# Sheet2.net
KiCad netlist of a schematic drawn in Altium Designer
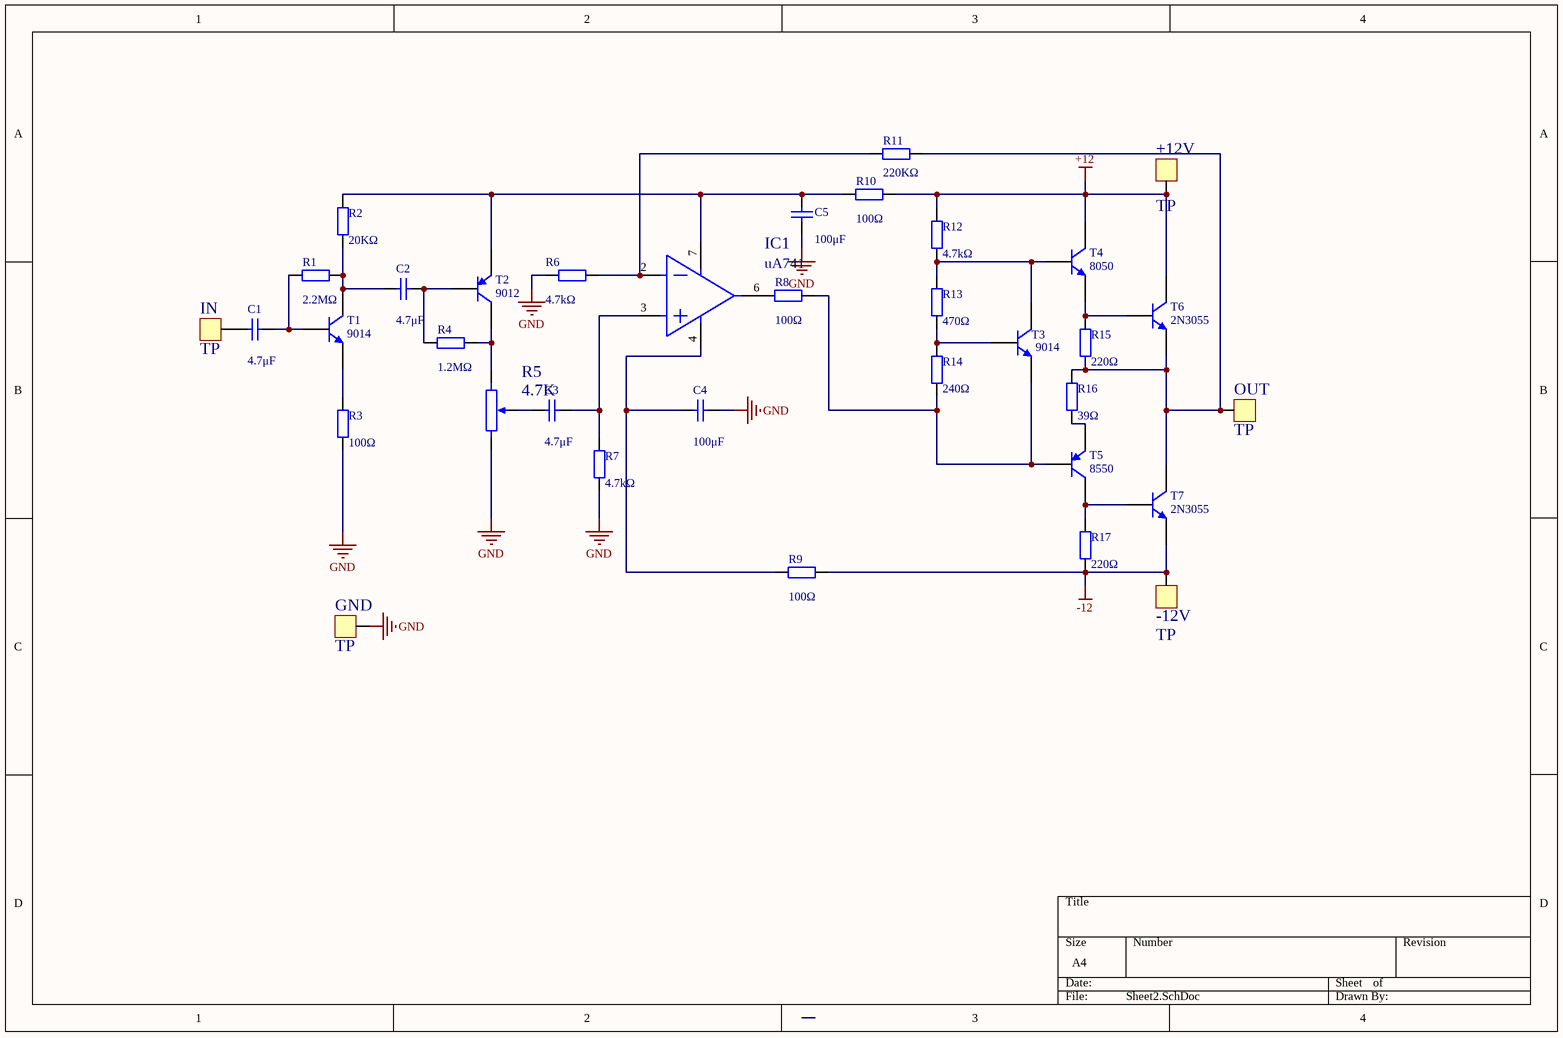
[diagram p0: Sheet2.SchDoc]

(export (version "E")
  (design (tool "Eeschema 10.0.6"))
  (components
    (comp (ref "+12V") (value "TP") (footprint "TP2") (libsource (lib "") (part "TP_2")))
    (comp (ref "-12V") (value "TP") (footprint "TP2") (libsource (lib "") (part "TP_3")))
    (comp (ref "C1")
      (value "4.7μF")
      (footprint "teach2018:CAPPR5-5x5")
      (description "Capacitor")
      (fields (field (name "PUBLISHER") "Altium Limited"))
      (libsource (lib "Miscellaneous Devices") (part "Cap"))
    )
    (comp (ref "C2")
      (value "4.7μF")
      (footprint "teach2018:CAPPR5-5x5")
      (description "Capacitor")
      (fields (field (name "PUBLISHER") "Altium Limited"))
      (libsource (lib "Miscellaneous Devices") (part "Cap"))
    )
    (comp (ref "C3")
      (value "4.7μF")
      (footprint "teach2018:CAPPR5-5x5")
      (description "Capacitor")
      (fields (field (name "PUBLISHER") "Altium Limited"))
      (libsource (lib "Miscellaneous Devices") (part "Cap"))
    )
    (comp (ref "C4")
      (value "100μF")
      (footprint "teach2018:CAPPR5-5x5")
      (description "Capacitor")
      (fields (field (name "PUBLISHER") "Altium Limited"))
      (libsource (lib "Miscellaneous Devices") (part "Cap"))
    )
    (comp (ref "C5")
      (value "100μF")
      (footprint "teach2018:CAPPR5-5x5")
      (description "Capacitor")
      (fields (field (name "PUBLISHER") "Altium Limited"))
      (libsource (lib "Miscellaneous Devices") (part "Cap"))
    )
    (comp (ref "GND") (value "TP") (footprint "TP2") (libsource (lib "teach2018") (part "TP")))
    (comp (ref "IC1")
      (value "uA741")
      (footprint "DIP-8")
      (description "OAP")
      (libsource (lib "teach2018") (part "uA741"))
    )
    (comp (ref "IN") (value "TP") (footprint "TP2") (libsource (lib "teach2018") (part "TP")))
    (comp (ref "OUT") (value "TP") (footprint "TP2") (libsource (lib "") (part "TP_1")))
    (comp (ref "R1")
      (value "2.2MΩ")
      (footprint "AXIAL-0.4")
      (description "Resistor")
      (fields (field (name "PUBLISHER") "Altium Limited"))
      (libsource (lib "") (part "Res2_1"))
    )
    (comp (ref "R2")
      (value "20KΩ")
      (footprint "AXIAL-0.4")
      (description "Resistor")
      (fields (field (name "PUBLISHER") "Altium Limited"))
      (libsource (lib "Miscellaneous Devices") (part "Res2"))
    )
    (comp (ref "R3")
      (value "100Ω")
      (footprint "AXIAL-0.4")
      (description "Resistor")
      (fields (field (name "PUBLISHER") "Altium Limited"))
      (libsource (lib "Miscellaneous Devices") (part "Res2"))
    )
    (comp (ref "R4")
      (value "1.2MΩ")
      (footprint "AXIAL-0.4")
      (description "Resistor")
      (fields (field (name "PUBLISHER") "Altium Limited"))
      (libsource (lib "") (part "Res2_1"))
    )
    (comp (ref "R5")
      (value "4.7K")
      (footprint "RPOT")
      (description "Potentiometer")
      (fields (field (name "Comment") "RPOT"))
      (libsource (lib "teach2018") (part "RPOT"))
    )
    (comp (ref "R6")
      (value "4.7kΩ")
      (footprint "AXIAL-0.4")
      (description "Resistor")
      (fields (field (name "PUBLISHER") "Altium Limited"))
      (libsource (lib "") (part "Res2_1"))
    )
    (comp (ref "R7")
      (value "4.7kΩ")
      (footprint "AXIAL-0.4")
      (description "Resistor")
      (fields (field (name "PUBLISHER") "Altium Limited"))
      (libsource (lib "Miscellaneous Devices") (part "Res2"))
    )
    (comp (ref "R8")
      (value "100Ω")
      (footprint "AXIAL-0.4")
      (description "Resistor")
      (fields (field (name "PUBLISHER") "Altium Limited"))
      (libsource (lib "") (part "Res2_1"))
    )
    (comp (ref "R9")
      (value "100Ω")
      (footprint "teach2018:AXIAL-0.4")
      (description "Resistor")
      (fields (field (name "PUBLISHER") "Altium Limited"))
      (libsource (lib "") (part "Res2_1"))
    )
    (comp (ref "R10")
      (value "100Ω")
      (footprint "AXIAL-0.4")
      (description "Resistor")
      (fields (field (name "PUBLISHER") "Altium Limited"))
      (libsource (lib "") (part "Res2_1"))
    )
    (comp (ref "R11")
      (value "220KΩ")
      (footprint "AXIAL-0.4")
      (description "Resistor")
      (fields (field (name "PUBLISHER") "Altium Limited"))
      (libsource (lib "") (part "Res2_1"))
    )
    (comp (ref "R12")
      (value "4.7kΩ")
      (footprint "AXIAL-0.4")
      (description "Resistor")
      (fields (field (name "PUBLISHER") "Altium Limited"))
      (libsource (lib "Miscellaneous Devices") (part "Res2"))
    )
    (comp (ref "R13")
      (value "470Ω")
      (footprint "AXIAL-0.4")
      (description "Resistor")
      (fields (field (name "PUBLISHER") "Altium Limited"))
      (libsource (lib "Miscellaneous Devices") (part "Res2"))
    )
    (comp (ref "R14")
      (value "240Ω")
      (footprint "AXIAL-0.4")
      (description "Resistor")
      (fields (field (name "PUBLISHER") "Altium Limited"))
      (libsource (lib "Miscellaneous Devices") (part "Res2"))
    )
    (comp (ref "R15")
      (value "220Ω")
      (footprint "AXIAL-0.4")
      (description "Resistor")
      (fields (field (name "PUBLISHER") "Altium Limited"))
      (libsource (lib "") (part "Res2_2"))
    )
    (comp (ref "R16")
      (value "39Ω")
      (footprint "AXIAL-0.4")
      (description "Resistor")
      (fields (field (name "PUBLISHER") "Altium Limited"))
      (libsource (lib "Miscellaneous Devices") (part "Res2"))
    )
    (comp (ref "R17")
      (value "220Ω")
      (footprint "AXIAL-0.4")
      (description "Resistor")
      (fields (field (name "PUBLISHER") "Altium Limited"))
      (libsource (lib "Miscellaneous Devices") (part "Res2"))
    )
    (comp (ref "T1")
      (value "9014")
      (footprint "teach2018:TANS")
      (description "NPN General Purpose Amplifier")
      (fields (field (name "PUBLISHER") "Altium Limited"))
      (libsource (lib "Miscellaneous Devices") (part "2N3904"))
    )
    (comp (ref "T2")
      (value "9012")
      (footprint "teach2018:TANS")
      (description "PNP General Purpose Amplifier")
      (fields (field (name "PUBLISHER") "Altium Limited"))
      (libsource (lib "Miscellaneous Devices") (part "2N3906"))
    )
    (comp (ref "T3")
      (value "9014")
      (footprint "teach2018:TANS")
      (description "NPN General Purpose Amplifier")
      (fields (field (name "PUBLISHER") "Altium Limited"))
      (libsource (lib "Miscellaneous Devices") (part "2N3904"))
    )
    (comp (ref "T4")
      (value "8050")
      (footprint "teach2018:TANS")
      (description "NPN General Purpose Amplifier")
      (fields (field (name "PUBLISHER") "Altium Limited"))
      (libsource (lib "Miscellaneous Devices") (part "2N3904"))
    )
    (comp (ref "T5")
      (value "8550")
      (footprint "teach2018:TANS")
      (description "PNP General Purpose Amplifier")
      (fields (field (name "PUBLISHER") "Altium Limited"))
      (libsource (lib "Miscellaneous Devices") (part "2N3906"))
    )
    (comp (ref "T6")
      (value "2N3055")
      (footprint "teach2018:TO-3")
      (description "NPN General Purpose Amplifier")
      (fields (field (name "PUBLISHER") "Altium Limited"))
      (libsource (lib "Miscellaneous Devices") (part "2N3904"))
    )
    (comp (ref "T7")
      (value "2N3055")
      (footprint "teach2018:TO-3")
      (description "NPN General Purpose Amplifier")
      (fields (field (name "PUBLISHER") "Altium Limited"))
      (libsource (lib "Miscellaneous Devices") (part "2N3904"))
    )
  )
  (nets
    (net (code "1") (name "+12") (class "Default")
      (node (ref "+12V") (pin "1") (pinfunction "1_1") (pintype "passive"))
      (node (ref "R10") (pin "2") (pinfunction "2_2") (pintype "passive"))
      (node (ref "R12") (pin "2") (pinfunction "2_2") (pintype "passive"))
      (node (ref "T4") (pin "3") (pinfunction "C_3") (pintype "passive"))
      (node (ref "T6") (pin "3") (pinfunction "C_3") (pintype "passive"))
    )
    (net (code "2") (name "-12") (class "Default")
      (node (ref "-12V") (pin "1") (pinfunction "1_1") (pintype "passive"))
      (node (ref "R17") (pin "1") (pinfunction "1_1") (pintype "passive"))
      (node (ref "R9") (pin "2") (pinfunction "2_2") (pintype "passive"))
      (node (ref "T7") (pin "1") (pinfunction "E_1") (pintype "passive"))
    )
    (net (code "3") (name "1") (class "Default")
      (node (ref "IC1") (pin "1") (pinfunction "1_1") (pintype "passive"))
    )
    (net (code "4") (name "8") (class "Default")
      (node (ref "IC1") (pin "8") (pinfunction "8_8") (pintype "passive"))
    )
    (net (code "5") (name "GND") (class "Default")
      (node (ref "C4") (pin "1") (pinfunction "1_1") (pintype "passive"))
      (node (ref "C5") (pin "1") (pinfunction "1_1") (pintype "passive"))
      (node (ref "GND") (pin "1") (pinfunction "1_1") (pintype "passive"))
      (node (ref "R3") (pin "1") (pinfunction "1_1") (pintype "passive"))
      (node (ref "R5") (pin "3") (pinfunction "BOT_3") (pintype "passive"))
      (node (ref "R6") (pin "1") (pinfunction "1_1") (pintype "passive"))
      (node (ref "R7") (pin "1") (pinfunction "1_1") (pintype "passive"))
    )
    (net (code "6") (name "Net-(C1-Pad1)") (class "Default")
      (node (ref "C1") (pin "1") (pinfunction "1_1") (pintype "passive"))
      (node (ref "IN") (pin "1") (pinfunction "1_1") (pintype "passive"))
    )
    (net (code "7") (name "Net-(C3-Pad2)") (class "Default")
      (node (ref "C3") (pin "2") (pinfunction "2_2") (pintype "passive"))
      (node (ref "IC1") (pin "3") (pinfunction "3_3") (pintype "passive"))
      (node (ref "R7") (pin "2") (pinfunction "2_2") (pintype "passive"))
    )
    (net (code "8") (name "Net-(C4-Pad2)") (class "Default")
      (node (ref "C4") (pin "2") (pinfunction "2_2") (pintype "passive"))
      (node (ref "IC1") (pin "4") (pinfunction "4_4") (pintype "passive"))
      (node (ref "R9") (pin "1") (pinfunction "1_1") (pintype "passive"))
    )
    (net (code "9") (name "Net-(IC1-Pad2)") (class "Default")
      (node (ref "IC1") (pin "2") (pinfunction "2_2") (pintype "passive"))
      (node (ref "R11") (pin "1") (pinfunction "1_1") (pintype "passive"))
      (node (ref "R6") (pin "2") (pinfunction "2_2") (pintype "passive"))
    )
    (net (code "10") (name "Net-(IC1-Pad6)") (class "Default")
      (node (ref "IC1") (pin "6") (pinfunction "6_6") (pintype "passive"))
      (node (ref "R8") (pin "1") (pinfunction "1_1") (pintype "passive"))
    )
    (net (code "11") (name "Net-(R5-TAP)") (class "Default")
      (node (ref "C3") (pin "1") (pinfunction "1_1") (pintype "passive"))
      (node (ref "R5") (pin "2") (pinfunction "TAP_2") (pintype "passive"))
    )
    (net (code "12") (name "Net-(R5-TOP)") (class "Default")
      (node (ref "R4") (pin "2") (pinfunction "2_2") (pintype "passive"))
      (node (ref "R5") (pin "1") (pinfunction "TOP_1") (pintype "passive"))
      (node (ref "T2") (pin "3") (pinfunction "C_3") (pintype "passive"))
    )
    (net (code "13") (name "Net-(T1-B)") (class "Default")
      (node (ref "C1") (pin "2") (pinfunction "2_2") (pintype "passive"))
      (node (ref "R1") (pin "1") (pinfunction "1_1") (pintype "passive"))
      (node (ref "T1") (pin "2") (pinfunction "B_2") (pintype "passive"))
    )
    (net (code "14") (name "Net-(T1-C)") (class "Default")
      (node (ref "C2") (pin "1") (pinfunction "1_1") (pintype "passive"))
      (node (ref "R1") (pin "2") (pinfunction "2_2") (pintype "passive"))
      (node (ref "R2") (pin "1") (pinfunction "1_1") (pintype "passive"))
      (node (ref "T1") (pin "3") (pinfunction "C_3") (pintype "passive"))
    )
    (net (code "15") (name "Net-(T1-E)") (class "Default")
      (node (ref "R3") (pin "2") (pinfunction "2_2") (pintype "passive"))
      (node (ref "T1") (pin "1") (pinfunction "E_1") (pintype "passive"))
    )
    (net (code "16") (name "Net-(T2-B)") (class "Default")
      (node (ref "C2") (pin "2") (pinfunction "2_2") (pintype "passive"))
      (node (ref "R4") (pin "1") (pinfunction "1_1") (pintype "passive"))
      (node (ref "T2") (pin "2") (pinfunction "B_2") (pintype "passive"))
    )
    (net (code "17") (name "Net-(T2-E)") (class "Default")
      (node (ref "C5") (pin "2") (pinfunction "2_2") (pintype "passive"))
      (node (ref "IC1") (pin "7") (pinfunction "7_7") (pintype "passive"))
      (node (ref "R10") (pin "1") (pinfunction "1_1") (pintype "passive"))
      (node (ref "R2") (pin "2") (pinfunction "2_2") (pintype "passive"))
      (node (ref "T2") (pin "1") (pinfunction "E_1") (pintype "passive"))
    )
    (net (code "18") (name "Net-(T3-B)") (class "Default")
      (node (ref "R13") (pin "1") (pinfunction "1_1") (pintype "passive"))
      (node (ref "R14") (pin "2") (pinfunction "2_2") (pintype "passive"))
      (node (ref "T3") (pin "2") (pinfunction "B_2") (pintype "passive"))
    )
    (net (code "19") (name "Net-(T3-C)") (class "Default")
      (node (ref "R12") (pin "1") (pinfunction "1_1") (pintype "passive"))
      (node (ref "R13") (pin "2") (pinfunction "2_2") (pintype "passive"))
      (node (ref "T3") (pin "3") (pinfunction "C_3") (pintype "passive"))
      (node (ref "T4") (pin "2") (pinfunction "B_2") (pintype "passive"))
    )
    (net (code "20") (name "Net-(T3-E)") (class "Default")
      (node (ref "R14") (pin "1") (pinfunction "1_1") (pintype "passive"))
      (node (ref "R8") (pin "2") (pinfunction "2_2") (pintype "passive"))
      (node (ref "T3") (pin "1") (pinfunction "E_1") (pintype "passive"))
      (node (ref "T5") (pin "2") (pinfunction "B_2") (pintype "passive"))
    )
    (net (code "21") (name "Net-(T4-E)") (class "Default")
      (node (ref "R15") (pin "1") (pinfunction "1_1") (pintype "passive"))
      (node (ref "T4") (pin "1") (pinfunction "E_1") (pintype "passive"))
      (node (ref "T6") (pin "2") (pinfunction "B_2") (pintype "passive"))
    )
    (net (code "22") (name "Net-(T5-C)") (class "Default")
      (node (ref "R17") (pin "2") (pinfunction "2_2") (pintype "passive"))
      (node (ref "T5") (pin "3") (pinfunction "C_3") (pintype "passive"))
      (node (ref "T7") (pin "2") (pinfunction "B_2") (pintype "passive"))
    )
    (net (code "23") (name "Net-(T5-E)") (class "Default")
      (node (ref "R16") (pin "1") (pinfunction "1_1") (pintype "passive"))
      (node (ref "T5") (pin "1") (pinfunction "E_1") (pintype "passive"))
    )
    (net (code "24") (name "Net-(T6-E)") (class "Default")
      (node (ref "OUT") (pin "1") (pinfunction "1_1") (pintype "passive"))
      (node (ref "R11") (pin "2") (pinfunction "2_2") (pintype "passive"))
      (node (ref "R15") (pin "2") (pinfunction "2_2") (pintype "passive"))
      (node (ref "R16") (pin "2") (pinfunction "2_2") (pintype "passive"))
      (node (ref "T6") (pin "1") (pinfunction "E_1") (pintype "passive"))
      (node (ref "T7") (pin "3") (pinfunction "C_3") (pintype "passive"))
    )
  )
)
